# Swarm.net
KiCad netlist of a schematic drawn in Altium Designer
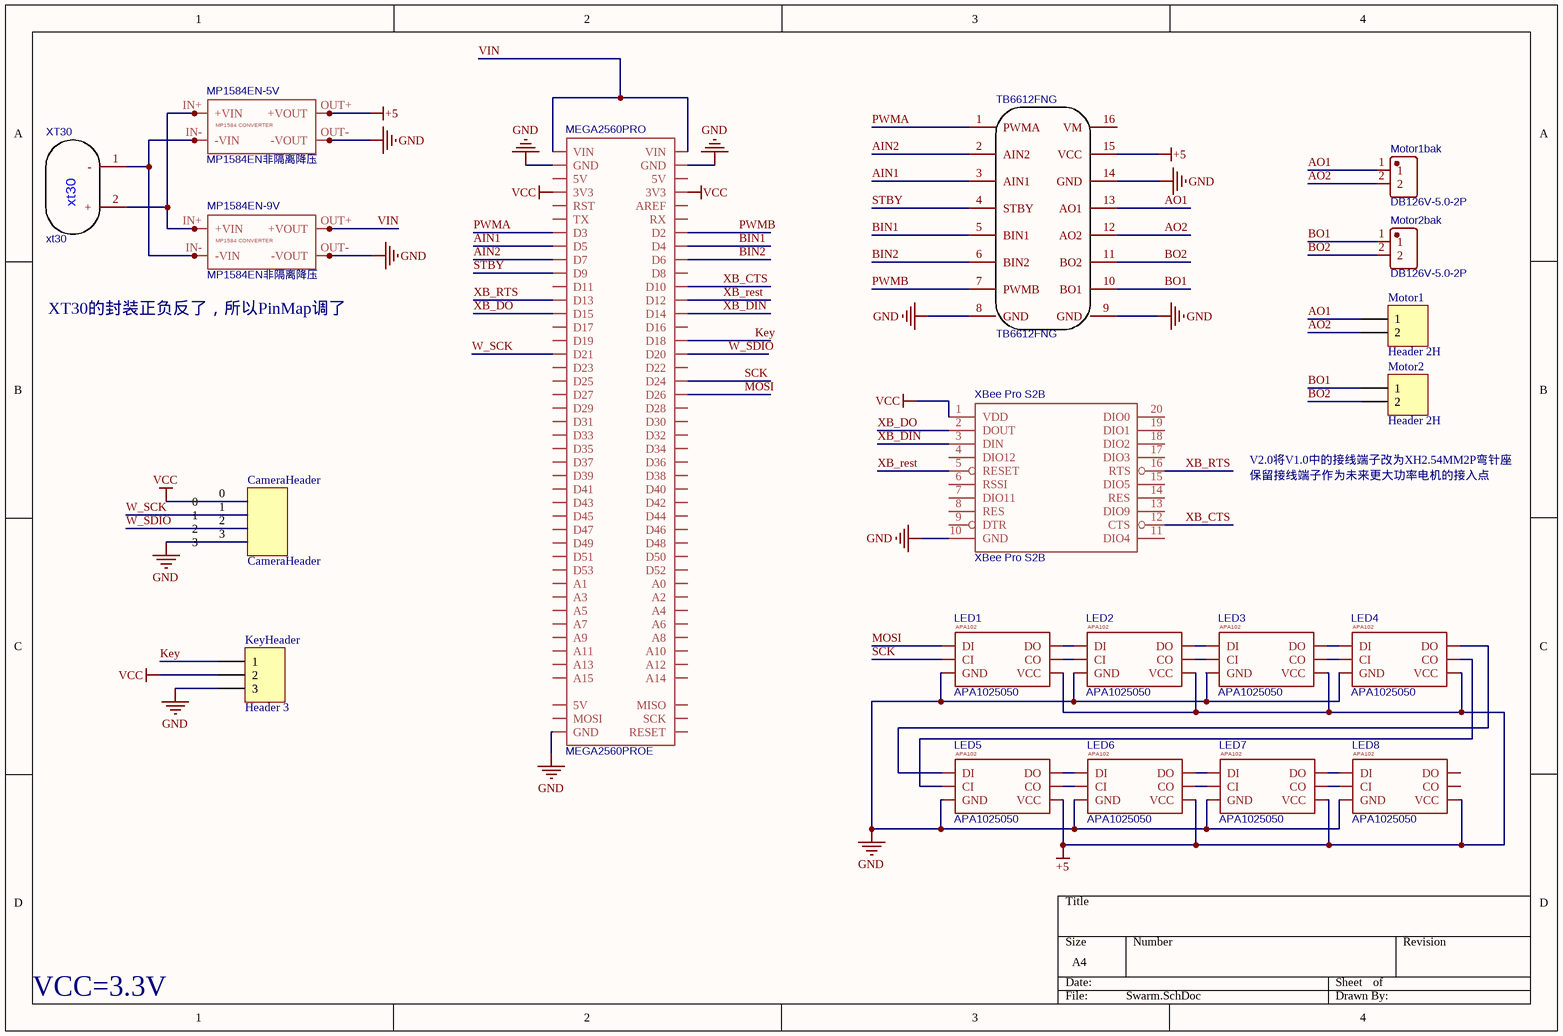
[diagram p0: Swarm.SchDoc]

(export (version "E")
  (design (tool "Eeschema 10.0.6"))
  (components
    (comp (ref "CameraHeader")
      (value "CameraHeader")
      (footprint "CameraHeader")
      (libsource (lib "CameraHeader") (part "Component_1"))
    )
    (comp (ref "KeyHeader")
      (value "Header 3")
      (footprint "HDR1X3")
      (description "Header, 3-Pin")
      (fields (field (name "PUBLISHER") "Altium Limited"))
      (libsource (lib "Miscellaneous Connectors") (part "Header 3"))
    )
    (comp (ref "LED1")
      (value "APA1025050")
      (footprint "APA102_5050")
      (libsource (lib "SwarmRobot") (part "APA1025050"))
    )
    (comp (ref "LED2")
      (value "APA1025050")
      (footprint "APA102_5050")
      (libsource (lib "SwarmRobot") (part "APA1025050"))
    )
    (comp (ref "LED3")
      (value "APA1025050")
      (footprint "APA102_5050")
      (libsource (lib "SwarmRobot") (part "APA1025050"))
    )
    (comp (ref "LED4")
      (value "APA1025050")
      (footprint "APA102_5050")
      (libsource (lib "SwarmRobot") (part "APA1025050"))
    )
    (comp (ref "LED5")
      (value "APA1025050")
      (footprint "APA102_5050")
      (libsource (lib "SwarmRobot") (part "APA1025050"))
    )
    (comp (ref "LED6")
      (value "APA1025050")
      (footprint "APA102_5050")
      (libsource (lib "SwarmRobot") (part "APA1025050"))
    )
    (comp (ref "LED7")
      (value "APA1025050")
      (footprint "APA102_5050")
      (libsource (lib "SwarmRobot") (part "APA1025050"))
    )
    (comp (ref "LED8")
      (value "APA1025050")
      (footprint "APA102_5050")
      (libsource (lib "SwarmRobot") (part "APA1025050"))
    )
    (comp (ref "MEGA2560PRO")
      (value "MEGA2560PROE")
      (footprint "MEGA2560PRO")
      (fields (field (name "CONTRIBUTOR") "westcowboy"))
      (libsource (lib "SwarmRobot") (part "MEGA2560PROE copy"))
    )
    (comp (ref "Motor1")
      (value "Header 2H")
      (footprint "HDR1X2H")
      (description "Header, 2-Pin, Right Angle")
      (fields (field (name "PUBLISHER") "Altium Limited"))
      (libsource (lib "Miscellaneous Connectors") (part "Header 2H"))
    )
    (comp (ref "Motor1bak")
      (value "DB126V-5.0-2P")
      (footprint "CONN-TH_2PIN-V-PITCH5.00-L_JL126-50002G01")
      (fields (field (name "BOM_SUPPLIER PART") "C395849") (field (name "CONTRIBUTOR") "LCSC"))
      (libsource (lib "SwarmRobot") (part "DB126V-5.0-2P"))
    )
    (comp (ref "Motor2")
      (value "Header 2H")
      (footprint "HDR1X2H")
      (description "Header, 2-Pin, Right Angle")
      (fields (field (name "PUBLISHER") "Altium Limited"))
      (libsource (lib "Miscellaneous Connectors") (part "Header 2H"))
    )
    (comp (ref "Motor2bak")
      (value "DB126V-5.0-2P")
      (footprint "CONN-TH_2PIN-V-PITCH5.00-L_JL126-50002G01")
      (fields (field (name "BOM_SUPPLIER PART") "C395849") (field (name "CONTRIBUTOR") "LCSC"))
      (libsource (lib "SwarmRobot") (part "DB126V-5.0-2P"))
    )
    (comp (ref "MP1584EN-5V")
      (value "MP1584EN非隔离降压")
      (footprint "MP1584_DC")
      (fields (field (name "CONTRIBUTOR") "zuwenz"))
      (libsource (lib "SwarmRobot") (part "MP1584EN非隔离降压"))
    )
    (comp (ref "MP1584EN-9V")
      (value "MP1584EN非隔离降压")
      (footprint "MP1584_DC")
      (fields (field (name "CONTRIBUTOR") "zuwenz"))
      (libsource (lib "SwarmRobot") (part "MP1584EN非隔离降压"))
    )
    (comp (ref "TB6612FNG")
      (value "TB6612FNG")
      (footprint "TB6612FNG")
      (fields (field (name "CONTRIBUTOR") "Lwj.bf"))
      (libsource (lib "TB6612") (part "TB6612FNG"))
    )
    (comp (ref "XBee Pro S2B")
      (value "XBee Pro S2B")
      (footprint "XBEE-1")
      (fields (field (name "CONTRIBUTOR") "niudvb"))
      (libsource (lib "SwarmRobot") (part "XBEE-1B1"))
    )
    (comp (ref "XT30")
      (value "xt30")
      (footprint "XT30 GONG")
      (fields (field (name "CONTRIBUTOR") "Weiwww"))
      (libsource (lib "SwarmRobot") (part "xt30"))
    )
  )
  (nets
    (net (code "1") (name "+5") (class "Default")
      (node (ref "LED1") (pin "1") (pinfunction "VCC_1") (pintype "passive"))
      (node (ref "LED2") (pin "1") (pinfunction "VCC_1") (pintype "passive"))
      (node (ref "LED3") (pin "1") (pinfunction "VCC_1") (pintype "passive"))
      (node (ref "LED4") (pin "1") (pinfunction "VCC_1") (pintype "passive"))
      (node (ref "LED5") (pin "1") (pinfunction "VCC_1") (pintype "passive"))
      (node (ref "LED6") (pin "1") (pinfunction "VCC_1") (pintype "passive"))
      (node (ref "LED7") (pin "1") (pinfunction "VCC_1") (pintype "passive"))
      (node (ref "LED8") (pin "1") (pinfunction "VCC_1") (pintype "passive"))
      (node (ref "MP1584EN-5V") (pin "OUT+") (pinfunction "+VOUT_OUT+") (pintype "passive"))
      (node (ref "MP1584EN-5V") (pin "OUT+@1") (pinfunction "+VOUT_OUT+@1") (pintype "passive"))
      (node (ref "TB6612FNG") (pin "15") (pinfunction "VCC_15") (pintype "passive"))
    )
    (net (code "2") (name "/AIN1") (class "Default")
      (node (ref "MEGA2560PRO") (pin "D5") (pinfunction "D5_D5") (pintype "passive"))
      (node (ref "TB6612FNG") (pin "3") (pinfunction "AIN1_3") (pintype "passive"))
    )
    (net (code "3") (name "/AIN2") (class "Default")
      (node (ref "MEGA2560PRO") (pin "D7") (pinfunction "D7_D7") (pintype "passive"))
      (node (ref "TB6612FNG") (pin "2") (pinfunction "AIN2_2") (pintype "passive"))
    )
    (net (code "4") (name "/AO1") (class "Default")
      (node (ref "Motor1") (pin "1") (pinfunction "1_1") (pintype "passive"))
      (node (ref "Motor1bak") (pin "1") (pinfunction "1_1") (pintype "passive"))
      (node (ref "TB6612FNG") (pin "13") (pinfunction "AO1_13") (pintype "passive"))
    )
    (net (code "5") (name "/AO2") (class "Default")
      (node (ref "Motor1") (pin "2") (pinfunction "2_2") (pintype "passive"))
      (node (ref "Motor1bak") (pin "2") (pinfunction "2_2") (pintype "passive"))
      (node (ref "TB6612FNG") (pin "12") (pinfunction "AO2_12") (pintype "passive"))
    )
    (net (code "6") (name "/BIN1") (class "Default")
      (node (ref "MEGA2560PRO") (pin "D4") (pinfunction "D4_D4") (pintype "passive"))
      (node (ref "TB6612FNG") (pin "5") (pinfunction "BIN1_5") (pintype "passive"))
    )
    (net (code "7") (name "/BIN2") (class "Default")
      (node (ref "MEGA2560PRO") (pin "D6") (pinfunction "D6_D6") (pintype "passive"))
      (node (ref "TB6612FNG") (pin "6") (pinfunction "BIN2_6") (pintype "passive"))
    )
    (net (code "8") (name "/BO1") (class "Default")
      (node (ref "Motor2") (pin "1") (pinfunction "1_1") (pintype "passive"))
      (node (ref "Motor2bak") (pin "1") (pinfunction "1_1") (pintype "passive"))
      (node (ref "TB6612FNG") (pin "10") (pinfunction "BO1_10") (pintype "passive"))
    )
    (net (code "9") (name "/BO2") (class "Default")
      (node (ref "Motor2") (pin "2") (pinfunction "2_2") (pintype "passive"))
      (node (ref "Motor2bak") (pin "2") (pinfunction "2_2") (pintype "passive"))
      (node (ref "TB6612FNG") (pin "11") (pinfunction "BO2_11") (pintype "passive"))
    )
    (net (code "10") (name "/Key") (class "Default")
      (node (ref "KeyHeader") (pin "1") (pinfunction "1_1") (pintype "passive"))
      (node (ref "MEGA2560PRO") (pin "D18") (pinfunction "D18_D18") (pintype "passive"))
    )
    (net (code "11") (name "/MOSI") (class "Default")
      (node (ref "LED1") (pin "4") (pinfunction "DI_4") (pintype "passive"))
      (node (ref "MEGA2560PRO") (pin "D26") (pinfunction "D26_D26") (pintype "passive"))
    )
    (net (code "12") (name "/PWMA") (class "Default")
      (node (ref "MEGA2560PRO") (pin "D3") (pinfunction "D3_D3") (pintype "passive"))
      (node (ref "TB6612FNG") (pin "1") (pinfunction "PWMA_1") (pintype "passive"))
    )
    (net (code "13") (name "/PWMB") (class "Default")
      (node (ref "MEGA2560PRO") (pin "D2") (pinfunction "D2_D2") (pintype "passive"))
      (node (ref "TB6612FNG") (pin "7") (pinfunction "PWMB_7") (pintype "passive"))
    )
    (net (code "14") (name "/SCK") (class "Default")
      (node (ref "LED1") (pin "5") (pinfunction "CI_5") (pintype "passive"))
      (node (ref "MEGA2560PRO") (pin "D24") (pinfunction "D24_D24") (pintype "passive"))
    )
    (net (code "15") (name "/STBY") (class "Default")
      (node (ref "MEGA2560PRO") (pin "D9") (pinfunction "D9_D9") (pintype "passive"))
      (node (ref "TB6612FNG") (pin "4") (pinfunction "STBY_4") (pintype "passive"))
    )
    (net (code "16") (name "/VIN") (class "Default")
      (node (ref "MEGA2560PRO") (pin "VIN@1") (pinfunction "VIN_VIN@1") (pintype "passive"))
      (node (ref "MEGA2560PRO") (pin "VIN@2") (pinfunction "VIN_VIN@2") (pintype "passive"))
      (node (ref "MP1584EN-9V") (pin "OUT+") (pinfunction "+VOUT_OUT+") (pintype "passive"))
      (node (ref "MP1584EN-9V") (pin "OUT+@1") (pinfunction "+VOUT_OUT+@1") (pintype "passive"))
    )
    (net (code "17") (name "/W_SCK") (class "Default")
      (node (ref "CameraHeader") (pin "1") (pinfunction "1_1") (pintype "passive"))
      (node (ref "MEGA2560PRO") (pin "D21") (pinfunction "D21_D21") (pintype "passive"))
    )
    (net (code "18") (name "/W_SDIO") (class "Default")
      (node (ref "CameraHeader") (pin "2") (pinfunction "2_2") (pintype "passive"))
      (node (ref "MEGA2560PRO") (pin "D20") (pinfunction "D20_D20") (pintype "passive"))
    )
    (net (code "19") (name "/XB_CTS") (class "Default")
      (node (ref "MEGA2560PRO") (pin "D10") (pinfunction "D10_D10") (pintype "passive"))
      (node (ref "XBee Pro S2B") (pin "12") (pinfunction "CTS_12") (pintype "passive"))
    )
    (net (code "20") (name "/XB_DIN") (class "Default")
      (node (ref "MEGA2560PRO") (pin "D14") (pinfunction "D14_D14") (pintype "passive"))
      (node (ref "XBee Pro S2B") (pin "3") (pinfunction "DIN_3") (pintype "passive"))
    )
    (net (code "21") (name "/XB_DO") (class "Default")
      (node (ref "MEGA2560PRO") (pin "D15") (pinfunction "D15_D15") (pintype "passive"))
      (node (ref "XBee Pro S2B") (pin "2") (pinfunction "DOUT_2") (pintype "passive"))
    )
    (net (code "22") (name "/XB_RTS") (class "Default")
      (node (ref "MEGA2560PRO") (pin "D13") (pinfunction "D13_D13") (pintype "passive"))
      (node (ref "XBee Pro S2B") (pin "16") (pinfunction "RTS_16") (pintype "passive"))
    )
    (net (code "23") (name "/XB_rest") (class "Default")
      (node (ref "MEGA2560PRO") (pin "D12") (pinfunction "D12_D12") (pintype "passive"))
      (node (ref "XBee Pro S2B") (pin "5") (pinfunction "RESET_5") (pintype "passive"))
    )
    (net (code "24") (name "GND") (class "Default")
      (node (ref "CameraHeader") (pin "3") (pinfunction "3_3") (pintype "passive"))
      (node (ref "KeyHeader") (pin "3") (pinfunction "3_3") (pintype "passive"))
      (node (ref "LED1") (pin "6") (pinfunction "GND_6") (pintype "passive"))
      (node (ref "LED2") (pin "6") (pinfunction "GND_6") (pintype "passive"))
      (node (ref "LED3") (pin "6") (pinfunction "GND_6") (pintype "passive"))
      (node (ref "LED4") (pin "6") (pinfunction "GND_6") (pintype "passive"))
      (node (ref "LED5") (pin "6") (pinfunction "GND_6") (pintype "passive"))
      (node (ref "LED6") (pin "6") (pinfunction "GND_6") (pintype "passive"))
      (node (ref "LED7") (pin "6") (pinfunction "GND_6") (pintype "passive"))
      (node (ref "LED8") (pin "6") (pinfunction "GND_6") (pintype "passive"))
      (node (ref "MEGA2560PRO") (pin "GND@1") (pinfunction "GND_GND@1") (pintype "passive"))
      (node (ref "MEGA2560PRO") (pin "GND@2") (pinfunction "GND_GND@2") (pintype "passive"))
      (node (ref "MEGA2560PRO") (pin "GND@3") (pinfunction "GND_GND@3") (pintype "passive"))
      (node (ref "MP1584EN-5V") (pin "OUT-") (pinfunction "-VOUT_OUT-") (pintype "passive"))
      (node (ref "MP1584EN-5V") (pin "OUT-@1") (pinfunction "-VOUT_OUT-@1") (pintype "passive"))
      (node (ref "MP1584EN-9V") (pin "OUT-") (pinfunction "-VOUT_OUT-") (pintype "passive"))
      (node (ref "MP1584EN-9V") (pin "OUT-@1") (pinfunction "-VOUT_OUT-@1") (pintype "passive"))
      (node (ref "TB6612FNG") (pin "14") (pinfunction "GND_14") (pintype "passive"))
      (node (ref "TB6612FNG") (pin "8") (pinfunction "GND_8") (pintype "passive"))
      (node (ref "TB6612FNG") (pin "9") (pinfunction "GND_9") (pintype "passive"))
      (node (ref "XBee Pro S2B") (pin "10") (pinfunction "GND_10") (pintype "passive"))
    )
    (net (code "25") (name "Net-(LED1-CO)") (class "Default")
      (node (ref "LED1") (pin "2") (pinfunction "CO_2") (pintype "passive"))
      (node (ref "LED2") (pin "5") (pinfunction "CI_5") (pintype "passive"))
    )
    (net (code "26") (name "Net-(LED1-DO)") (class "Default")
      (node (ref "LED1") (pin "3") (pinfunction "DO_3") (pintype "passive"))
      (node (ref "LED2") (pin "4") (pinfunction "DI_4") (pintype "passive"))
    )
    (net (code "27") (name "Net-(LED2-CO)") (class "Default")
      (node (ref "LED2") (pin "2") (pinfunction "CO_2") (pintype "passive"))
      (node (ref "LED3") (pin "5") (pinfunction "CI_5") (pintype "passive"))
    )
    (net (code "28") (name "Net-(LED2-DO)") (class "Default")
      (node (ref "LED2") (pin "3") (pinfunction "DO_3") (pintype "passive"))
      (node (ref "LED3") (pin "4") (pinfunction "DI_4") (pintype "passive"))
    )
    (net (code "29") (name "Net-(LED3-CO)") (class "Default")
      (node (ref "LED3") (pin "2") (pinfunction "CO_2") (pintype "passive"))
      (node (ref "LED4") (pin "5") (pinfunction "CI_5") (pintype "passive"))
    )
    (net (code "30") (name "Net-(LED3-DO)") (class "Default")
      (node (ref "LED3") (pin "3") (pinfunction "DO_3") (pintype "passive"))
      (node (ref "LED4") (pin "4") (pinfunction "DI_4") (pintype "passive"))
    )
    (net (code "31") (name "Net-(LED4-CO)") (class "Default")
      (node (ref "LED4") (pin "2") (pinfunction "CO_2") (pintype "passive"))
      (node (ref "LED5") (pin "5") (pinfunction "CI_5") (pintype "passive"))
    )
    (net (code "32") (name "Net-(LED4-DO)") (class "Default")
      (node (ref "LED4") (pin "3") (pinfunction "DO_3") (pintype "passive"))
      (node (ref "LED5") (pin "4") (pinfunction "DI_4") (pintype "passive"))
    )
    (net (code "33") (name "Net-(LED5-CO)") (class "Default")
      (node (ref "LED5") (pin "2") (pinfunction "CO_2") (pintype "passive"))
      (node (ref "LED6") (pin "5") (pinfunction "CI_5") (pintype "passive"))
    )
    (net (code "34") (name "Net-(LED5-DO)") (class "Default")
      (node (ref "LED5") (pin "3") (pinfunction "DO_3") (pintype "passive"))
      (node (ref "LED6") (pin "4") (pinfunction "DI_4") (pintype "passive"))
    )
    (net (code "35") (name "Net-(LED6-CO)") (class "Default")
      (node (ref "LED6") (pin "2") (pinfunction "CO_2") (pintype "passive"))
      (node (ref "LED7") (pin "5") (pinfunction "CI_5") (pintype "passive"))
    )
    (net (code "36") (name "Net-(LED6-DO)") (class "Default")
      (node (ref "LED6") (pin "3") (pinfunction "DO_3") (pintype "passive"))
      (node (ref "LED7") (pin "4") (pinfunction "DI_4") (pintype "passive"))
    )
    (net (code "37") (name "Net-(LED7-CO)") (class "Default")
      (node (ref "LED7") (pin "2") (pinfunction "CO_2") (pintype "passive"))
      (node (ref "LED8") (pin "5") (pinfunction "CI_5") (pintype "passive"))
    )
    (net (code "38") (name "Net-(LED7-DO)") (class "Default")
      (node (ref "LED7") (pin "3") (pinfunction "DO_3") (pintype "passive"))
      (node (ref "LED8") (pin "4") (pinfunction "DI_4") (pintype "passive"))
    )
    (net (code "39") (name "Net-(XT30-+)") (class "Default")
      (node (ref "MP1584EN-5V") (pin "IN+") (pinfunction "+VIN_IN+") (pintype "passive"))
      (node (ref "MP1584EN-5V") (pin "IN+@1") (pinfunction "+VIN_IN+@1") (pintype "passive"))
      (node (ref "MP1584EN-9V") (pin "IN+") (pinfunction "+VIN_IN+") (pintype "passive"))
      (node (ref "MP1584EN-9V") (pin "IN+@1") (pinfunction "+VIN_IN+@1") (pintype "passive"))
      (node (ref "XT30") (pin "2") (pinfunction "+_2") (pintype "passive"))
    )
    (net (code "40") (name "Net-(XT30--)") (class "Default")
      (node (ref "MP1584EN-5V") (pin "IN-") (pinfunction "-VIN_IN-") (pintype "passive"))
      (node (ref "MP1584EN-5V") (pin "IN-@1") (pinfunction "-VIN_IN-@1") (pintype "passive"))
      (node (ref "MP1584EN-9V") (pin "IN-") (pinfunction "-VIN_IN-") (pintype "passive"))
      (node (ref "MP1584EN-9V") (pin "IN-@1") (pinfunction "-VIN_IN-@1") (pintype "passive"))
      (node (ref "XT30") (pin "1") (pinfunction "-_1") (pintype "passive"))
    )
    (net (code "41") (name "VCC") (class "Default")
      (node (ref "CameraHeader") (pin "0") (pinfunction "0_0") (pintype "passive"))
      (node (ref "KeyHeader") (pin "2") (pinfunction "2_2") (pintype "passive"))
      (node (ref "MEGA2560PRO") (pin "3V3@1") (pinfunction "3V3_3V3@1") (pintype "passive"))
      (node (ref "MEGA2560PRO") (pin "3V3@2") (pinfunction "3V3_3V3@2") (pintype "passive"))
      (node (ref "XBee Pro S2B") (pin "1") (pinfunction "VDD_1") (pintype "passive"))
    )
    (net (code "42") (name "unconnected-(LED8-CO-Pad2)") (class "Default")
      (node (ref "LED8") (pin "2") (pinfunction "CO_2") (pintype "passive"))
    )
    (net (code "43") (name "unconnected-(LED8-DO-Pad3)") (class "Default")
      (node (ref "LED8") (pin "3") (pinfunction "DO_3") (pintype "passive"))
    )
    (net (code "44") (name "unconnected-(MEGA2560PRO-5V-Pad5V@1)") (class "Default")
      (node (ref "MEGA2560PRO") (pin "5V@1") (pinfunction "5V_5V@1") (pintype "passive"))
    )
    (net (code "45") (name "unconnected-(MEGA2560PRO-5V-Pad5V@2)") (class "Default")
      (node (ref "MEGA2560PRO") (pin "5V@2") (pinfunction "5V_5V@2") (pintype "passive"))
    )
    (net (code "46") (name "unconnected-(MEGA2560PRO-5V-Pad5V@3)") (class "Default")
      (node (ref "MEGA2560PRO") (pin "5V@3") (pinfunction "5V_5V@3") (pintype "passive"))
    )
    (net (code "47") (name "unconnected-(MEGA2560PRO-PadA0)") (class "Default")
      (node (ref "MEGA2560PRO") (pin "A0") (pinfunction "A0_A0") (pintype "passive"))
    )
    (net (code "48") (name "unconnected-(MEGA2560PRO-PadA1)") (class "Default")
      (node (ref "MEGA2560PRO") (pin "A1") (pinfunction "A1_A1") (pintype "passive"))
    )
    (net (code "49") (name "unconnected-(MEGA2560PRO-PadA2)") (class "Default")
      (node (ref "MEGA2560PRO") (pin "A2") (pinfunction "A2_A2") (pintype "passive"))
    )
    (net (code "50") (name "unconnected-(MEGA2560PRO-PadA3)") (class "Default")
      (node (ref "MEGA2560PRO") (pin "A3") (pinfunction "A3_A3") (pintype "passive"))
    )
    (net (code "51") (name "unconnected-(MEGA2560PRO-PadA4)") (class "Default")
      (node (ref "MEGA2560PRO") (pin "A4") (pinfunction "A4_A4") (pintype "passive"))
    )
    (net (code "52") (name "unconnected-(MEGA2560PRO-PadA5)") (class "Default")
      (node (ref "MEGA2560PRO") (pin "A5") (pinfunction "A5_A5") (pintype "passive"))
    )
    (net (code "53") (name "unconnected-(MEGA2560PRO-PadA6)") (class "Default")
      (node (ref "MEGA2560PRO") (pin "A6") (pinfunction "A6_A6") (pintype "passive"))
    )
    (net (code "54") (name "unconnected-(MEGA2560PRO-PadA7)") (class "Default")
      (node (ref "MEGA2560PRO") (pin "A7") (pinfunction "A7_A7") (pintype "passive"))
    )
    (net (code "55") (name "unconnected-(MEGA2560PRO-PadA8)") (class "Default")
      (node (ref "MEGA2560PRO") (pin "A8") (pinfunction "A8_A8") (pintype "passive"))
    )
    (net (code "56") (name "unconnected-(MEGA2560PRO-PadA9)") (class "Default")
      (node (ref "MEGA2560PRO") (pin "A9") (pinfunction "A9_A9") (pintype "passive"))
    )
    (net (code "57") (name "unconnected-(MEGA2560PRO-PadA10)") (class "Default")
      (node (ref "MEGA2560PRO") (pin "A10") (pinfunction "A10_A10") (pintype "passive"))
    )
    (net (code "58") (name "unconnected-(MEGA2560PRO-PadA11)") (class "Default")
      (node (ref "MEGA2560PRO") (pin "A11") (pinfunction "A11_A11") (pintype "passive"))
    )
    (net (code "59") (name "unconnected-(MEGA2560PRO-PadA12)") (class "Default")
      (node (ref "MEGA2560PRO") (pin "A12") (pinfunction "A12_A12") (pintype "passive"))
    )
    (net (code "60") (name "unconnected-(MEGA2560PRO-PadA13)") (class "Default")
      (node (ref "MEGA2560PRO") (pin "A13") (pinfunction "A13_A13") (pintype "passive"))
    )
    (net (code "61") (name "unconnected-(MEGA2560PRO-PadA14)") (class "Default")
      (node (ref "MEGA2560PRO") (pin "A14") (pinfunction "A14_A14") (pintype "passive"))
    )
    (net (code "62") (name "unconnected-(MEGA2560PRO-PadA15)") (class "Default")
      (node (ref "MEGA2560PRO") (pin "A15") (pinfunction "A15_A15") (pintype "passive"))
    )
    (net (code "63") (name "unconnected-(MEGA2560PRO-PadAREF)") (class "Default")
      (node (ref "MEGA2560PRO") (pin "AREF") (pinfunction "AREF_AREF") (pintype "passive"))
    )
    (net (code "64") (name "unconnected-(MEGA2560PRO-PadD8)") (class "Default")
      (node (ref "MEGA2560PRO") (pin "D8") (pinfunction "D8_D8") (pintype "passive"))
    )
    (net (code "65") (name "unconnected-(MEGA2560PRO-PadD11)") (class "Default")
      (node (ref "MEGA2560PRO") (pin "D11") (pinfunction "D11_D11") (pintype "passive"))
    )
    (net (code "66") (name "unconnected-(MEGA2560PRO-PadD16)") (class "Default")
      (node (ref "MEGA2560PRO") (pin "D16") (pinfunction "D16_D16") (pintype "passive"))
    )
    (net (code "67") (name "unconnected-(MEGA2560PRO-PadD17)") (class "Default")
      (node (ref "MEGA2560PRO") (pin "D17") (pinfunction "D17_D17") (pintype "passive"))
    )
    (net (code "68") (name "unconnected-(MEGA2560PRO-PadD19)") (class "Default")
      (node (ref "MEGA2560PRO") (pin "D19") (pinfunction "D19_D19") (pintype "passive"))
    )
    (net (code "69") (name "unconnected-(MEGA2560PRO-PadD22)") (class "Default")
      (node (ref "MEGA2560PRO") (pin "D22") (pinfunction "D22_D22") (pintype "passive"))
    )
    (net (code "70") (name "unconnected-(MEGA2560PRO-PadD23)") (class "Default")
      (node (ref "MEGA2560PRO") (pin "D23") (pinfunction "D23_D23") (pintype "passive"))
    )
    (net (code "71") (name "unconnected-(MEGA2560PRO-PadD25)") (class "Default")
      (node (ref "MEGA2560PRO") (pin "D25") (pinfunction "D25_D25") (pintype "passive"))
    )
    (net (code "72") (name "unconnected-(MEGA2560PRO-PadD27)") (class "Default")
      (node (ref "MEGA2560PRO") (pin "D27") (pinfunction "D27_D27") (pintype "passive"))
    )
    (net (code "73") (name "unconnected-(MEGA2560PRO-PadD28)") (class "Default")
      (node (ref "MEGA2560PRO") (pin "D28") (pinfunction "D28_D28") (pintype "passive"))
    )
    (net (code "74") (name "unconnected-(MEGA2560PRO-PadD29)") (class "Default")
      (node (ref "MEGA2560PRO") (pin "D29") (pinfunction "D29_D29") (pintype "passive"))
    )
    (net (code "75") (name "unconnected-(MEGA2560PRO-PadD30)") (class "Default")
      (node (ref "MEGA2560PRO") (pin "D30") (pinfunction "D30_D30") (pintype "passive"))
    )
    (net (code "76") (name "unconnected-(MEGA2560PRO-PadD31)") (class "Default")
      (node (ref "MEGA2560PRO") (pin "D31") (pinfunction "D31_D31") (pintype "passive"))
    )
    (net (code "77") (name "unconnected-(MEGA2560PRO-PadD32)") (class "Default")
      (node (ref "MEGA2560PRO") (pin "D32") (pinfunction "D32_D32") (pintype "passive"))
    )
    (net (code "78") (name "unconnected-(MEGA2560PRO-PadD33)") (class "Default")
      (node (ref "MEGA2560PRO") (pin "D33") (pinfunction "D33_D33") (pintype "passive"))
    )
    (net (code "79") (name "unconnected-(MEGA2560PRO-PadD34)") (class "Default")
      (node (ref "MEGA2560PRO") (pin "D34") (pinfunction "D34_D34") (pintype "passive"))
    )
    (net (code "80") (name "unconnected-(MEGA2560PRO-PadD35)") (class "Default")
      (node (ref "MEGA2560PRO") (pin "D35") (pinfunction "D35_D35") (pintype "passive"))
    )
    (net (code "81") (name "unconnected-(MEGA2560PRO-PadD36)") (class "Default")
      (node (ref "MEGA2560PRO") (pin "D36") (pinfunction "D36_D36") (pintype "passive"))
    )
    (net (code "82") (name "unconnected-(MEGA2560PRO-PadD37)") (class "Default")
      (node (ref "MEGA2560PRO") (pin "D37") (pinfunction "D37_D37") (pintype "passive"))
    )
    (net (code "83") (name "unconnected-(MEGA2560PRO-PadD38)") (class "Default")
      (node (ref "MEGA2560PRO") (pin "D38") (pinfunction "D38_D38") (pintype "passive"))
    )
    (net (code "84") (name "unconnected-(MEGA2560PRO-PadD39)") (class "Default")
      (node (ref "MEGA2560PRO") (pin "D39") (pinfunction "D39_D39") (pintype "passive"))
    )
    (net (code "85") (name "unconnected-(MEGA2560PRO-PadD40)") (class "Default")
      (node (ref "MEGA2560PRO") (pin "D40") (pinfunction "D40_D40") (pintype "passive"))
    )
    (net (code "86") (name "unconnected-(MEGA2560PRO-PadD41)") (class "Default")
      (node (ref "MEGA2560PRO") (pin "D41") (pinfunction "D41_D41") (pintype "passive"))
    )
    (net (code "87") (name "unconnected-(MEGA2560PRO-PadD42)") (class "Default")
      (node (ref "MEGA2560PRO") (pin "D42") (pinfunction "D42_D42") (pintype "passive"))
    )
    (net (code "88") (name "unconnected-(MEGA2560PRO-PadD43)") (class "Default")
      (node (ref "MEGA2560PRO") (pin "D43") (pinfunction "D43_D43") (pintype "passive"))
    )
    (net (code "89") (name "unconnected-(MEGA2560PRO-PadD44)") (class "Default")
      (node (ref "MEGA2560PRO") (pin "D44") (pinfunction "D44_D44") (pintype "passive"))
    )
    (net (code "90") (name "unconnected-(MEGA2560PRO-PadD45)") (class "Default")
      (node (ref "MEGA2560PRO") (pin "D45") (pinfunction "D45_D45") (pintype "passive"))
    )
    (net (code "91") (name "unconnected-(MEGA2560PRO-PadD46)") (class "Default")
      (node (ref "MEGA2560PRO") (pin "D46") (pinfunction "D46_D46") (pintype "passive"))
    )
    (net (code "92") (name "unconnected-(MEGA2560PRO-PadD47)") (class "Default")
      (node (ref "MEGA2560PRO") (pin "D47") (pinfunction "D47_D47") (pintype "passive"))
    )
    (net (code "93") (name "unconnected-(MEGA2560PRO-PadD48)") (class "Default")
      (node (ref "MEGA2560PRO") (pin "D48") (pinfunction "D48_D48") (pintype "passive"))
    )
    (net (code "94") (name "unconnected-(MEGA2560PRO-PadD49)") (class "Default")
      (node (ref "MEGA2560PRO") (pin "D49") (pinfunction "D49_D49") (pintype "passive"))
    )
    (net (code "95") (name "unconnected-(MEGA2560PRO-PadD50)") (class "Default")
      (node (ref "MEGA2560PRO") (pin "D50") (pinfunction "D50_D50") (pintype "passive"))
    )
    (net (code "96") (name "unconnected-(MEGA2560PRO-PadD51)") (class "Default")
      (node (ref "MEGA2560PRO") (pin "D51") (pinfunction "D51_D51") (pintype "passive"))
    )
    (net (code "97") (name "unconnected-(MEGA2560PRO-PadD52)") (class "Default")
      (node (ref "MEGA2560PRO") (pin "D52") (pinfunction "D52_D52") (pintype "passive"))
    )
    (net (code "98") (name "unconnected-(MEGA2560PRO-PadD53)") (class "Default")
      (node (ref "MEGA2560PRO") (pin "D53") (pinfunction "D53_D53") (pintype "passive"))
    )
    (net (code "99") (name "unconnected-(MEGA2560PRO-PadMISO)") (class "Default")
      (node (ref "MEGA2560PRO") (pin "MISO") (pinfunction "MISO_MISO") (pintype "passive"))
    )
    (net (code "100") (name "unconnected-(MEGA2560PRO-PadMOSI)") (class "Default")
      (node (ref "MEGA2560PRO") (pin "MOSI") (pinfunction "MOSI_MOSI") (pintype "passive"))
    )
    (net (code "101") (name "unconnected-(MEGA2560PRO-PadRESET)") (class "Default")
      (node (ref "MEGA2560PRO") (pin "RESET") (pinfunction "RESET_RESET") (pintype "passive"))
    )
    (net (code "102") (name "unconnected-(MEGA2560PRO-PadRST)") (class "Default")
      (node (ref "MEGA2560PRO") (pin "RST") (pinfunction "RST_RST") (pintype "passive"))
    )
    (net (code "103") (name "unconnected-(MEGA2560PRO-PadRX)") (class "Default")
      (node (ref "MEGA2560PRO") (pin "RX") (pinfunction "RX_RX") (pintype "passive"))
    )
    (net (code "104") (name "unconnected-(MEGA2560PRO-PadSCK)") (class "Default")
      (node (ref "MEGA2560PRO") (pin "SCK") (pinfunction "SCK_SCK") (pintype "passive"))
    )
    (net (code "105") (name "unconnected-(MEGA2560PRO-PadTX)") (class "Default")
      (node (ref "MEGA2560PRO") (pin "TX") (pinfunction "TX_TX") (pintype "passive"))
    )
    (net (code "106") (name "unconnected-(TB6612FNG-VM-Pad16)") (class "Default")
      (node (ref "TB6612FNG") (pin "16") (pinfunction "VM_16") (pintype "passive"))
    )
    (net (code "107") (name "unconnected-(XBee Pro S2B-DIO0-Pad20)") (class "Default")
      (node (ref "XBee Pro S2B") (pin "20") (pinfunction "DIO0_20") (pintype "passive"))
    )
    (net (code "108") (name "unconnected-(XBee Pro S2B-DIO1-Pad19)") (class "Default")
      (node (ref "XBee Pro S2B") (pin "19") (pinfunction "DIO1_19") (pintype "passive"))
    )
    (net (code "109") (name "unconnected-(XBee Pro S2B-DIO2-Pad18)") (class "Default")
      (node (ref "XBee Pro S2B") (pin "18") (pinfunction "DIO2_18") (pintype "passive"))
    )
    (net (code "110") (name "unconnected-(XBee Pro S2B-DIO3-Pad17)") (class "Default")
      (node (ref "XBee Pro S2B") (pin "17") (pinfunction "DIO3_17") (pintype "passive"))
    )
    (net (code "111") (name "unconnected-(XBee Pro S2B-DIO4-Pad11)") (class "Default")
      (node (ref "XBee Pro S2B") (pin "11") (pinfunction "DIO4_11") (pintype "passive"))
    )
    (net (code "112") (name "unconnected-(XBee Pro S2B-DIO5-Pad15)") (class "Default")
      (node (ref "XBee Pro S2B") (pin "15") (pinfunction "DIO5_15") (pintype "passive"))
    )
    (net (code "113") (name "unconnected-(XBee Pro S2B-DIO9-Pad13)") (class "Default")
      (node (ref "XBee Pro S2B") (pin "13") (pinfunction "DIO9_13") (pintype "passive"))
    )
    (net (code "114") (name "unconnected-(XBee Pro S2B-DIO11-Pad7)") (class "Default")
      (node (ref "XBee Pro S2B") (pin "7") (pinfunction "DIO11_7") (pintype "passive"))
    )
    (net (code "115") (name "unconnected-(XBee Pro S2B-DIO12-Pad4)") (class "Default")
      (node (ref "XBee Pro S2B") (pin "4") (pinfunction "DIO12_4") (pintype "passive"))
    )
    (net (code "116") (name "unconnected-(XBee Pro S2B-DTR-Pad9)") (class "Default")
      (node (ref "XBee Pro S2B") (pin "9") (pinfunction "DTR_9") (pintype "passive"))
    )
    (net (code "117") (name "unconnected-(XBee Pro S2B-RES-Pad8)") (class "Default")
      (node (ref "XBee Pro S2B") (pin "8") (pinfunction "RES_8") (pintype "passive"))
    )
    (net (code "118") (name "unconnected-(XBee Pro S2B-RES-Pad14)") (class "Default")
      (node (ref "XBee Pro S2B") (pin "14") (pinfunction "RES_14") (pintype "passive"))
    )
    (net (code "119") (name "unconnected-(XBee Pro S2B-RSSI-Pad6)") (class "Default")
      (node (ref "XBee Pro S2B") (pin "6") (pinfunction "RSSI_6") (pintype "passive"))
    )
  )
)
